# QSPI_FLASH.net
KiCad netlist of a schematic drawn in Altium Designer
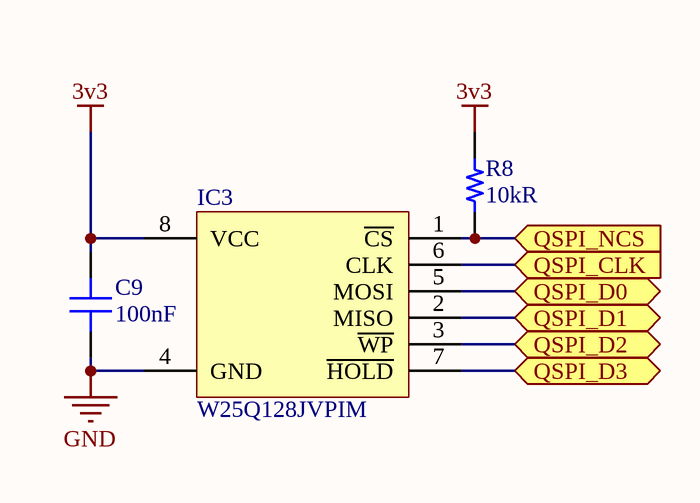
[diagram p0: QSPI FLASH.SchDoc]

(export (version "E")
  (design (tool "Eeschema 10.0.6"))
  (components
    (comp (ref "C9")
      (value "100nF")
      (footprint "CAP 0603/1608")
      (description "Ceramic, SMT Capacitor")
      (fields
        (field (name "MANUFACTURER") "Samsung")
        (field (name "MANUFACTURER PART NUMBER") "CL10B104JB8NNNC")
      )
      (libsource (lib "yildizIoT Library") (part "Capacitor - Ceramic"))
    )
    (comp (ref "IC3")
      (value "W25Q128JVPIM")
      (footprint "WINBOND WSON-8 6x5mm")
      (fields (field (name "MANUFACTURER") "Winbond"))
      (libsource (lib "yildizIoT Library") (part "WINBOND FLASH SPI 8PIN"))
    )
    (comp (ref "R8")
      (value "10kR")
      (footprint "RES 0603/1608")
      (description "Ceramic, SMT Capacitor")
      (fields
        (field (name "MANUFACTURER") "Stackpole Electronics")
        (field (name "MANUFACTURER PART NUMBER") "RNCP0603FTD10K0")
      )
      (libsource (lib "yildizIoT Library") (part "Resistor_Chip"))
    )
  )
  (nets
    (net (code "1") (name "/QSPI_CLK") (class "Default")
      (node (ref "IC3") (pin "6") (pinfunction "CLK_6") (pintype "passive"))
    )
    (net (code "2") (name "/QSPI_D0") (class "Default")
      (node (ref "IC3") (pin "5") (pinfunction "MOSI_5") (pintype "passive"))
    )
    (net (code "3") (name "/QSPI_D1") (class "Default")
      (node (ref "IC3") (pin "2") (pinfunction "MISO_2") (pintype "passive"))
    )
    (net (code "4") (name "/QSPI_D2") (class "Default")
      (node (ref "IC3") (pin "3") (pinfunction "~{WP}_3") (pintype "passive"))
    )
    (net (code "5") (name "/QSPI_D3") (class "Default")
      (node (ref "IC3") (pin "7") (pinfunction "~{HOLD}_7") (pintype "passive"))
    )
    (net (code "6") (name "/QSPI_NCS") (class "Default")
      (node (ref "IC3") (pin "1") (pinfunction "~{CS}_1") (pintype "passive"))
      (node (ref "R8") (pin "1") (pinfunction "1_1") (pintype "passive"))
    )
    (net (code "7") (name "3v3") (class "Default")
      (node (ref "C9") (pin "1") (pinfunction "1_1") (pintype "passive"))
      (node (ref "IC3") (pin "8") (pinfunction "VCC_8") (pintype "passive"))
      (node (ref "R8") (pin "2") (pinfunction "2_2") (pintype "passive"))
    )
    (net (code "8") (name "GND") (class "Default")
      (node (ref "C9") (pin "2") (pinfunction "2_2") (pintype "passive"))
      (node (ref "IC3") (pin "4") (pinfunction "GND_4") (pintype "passive"))
    )
  )
)
